# MOTORDEMO.net
KiCad netlist of a schematic drawn in Altium Designer
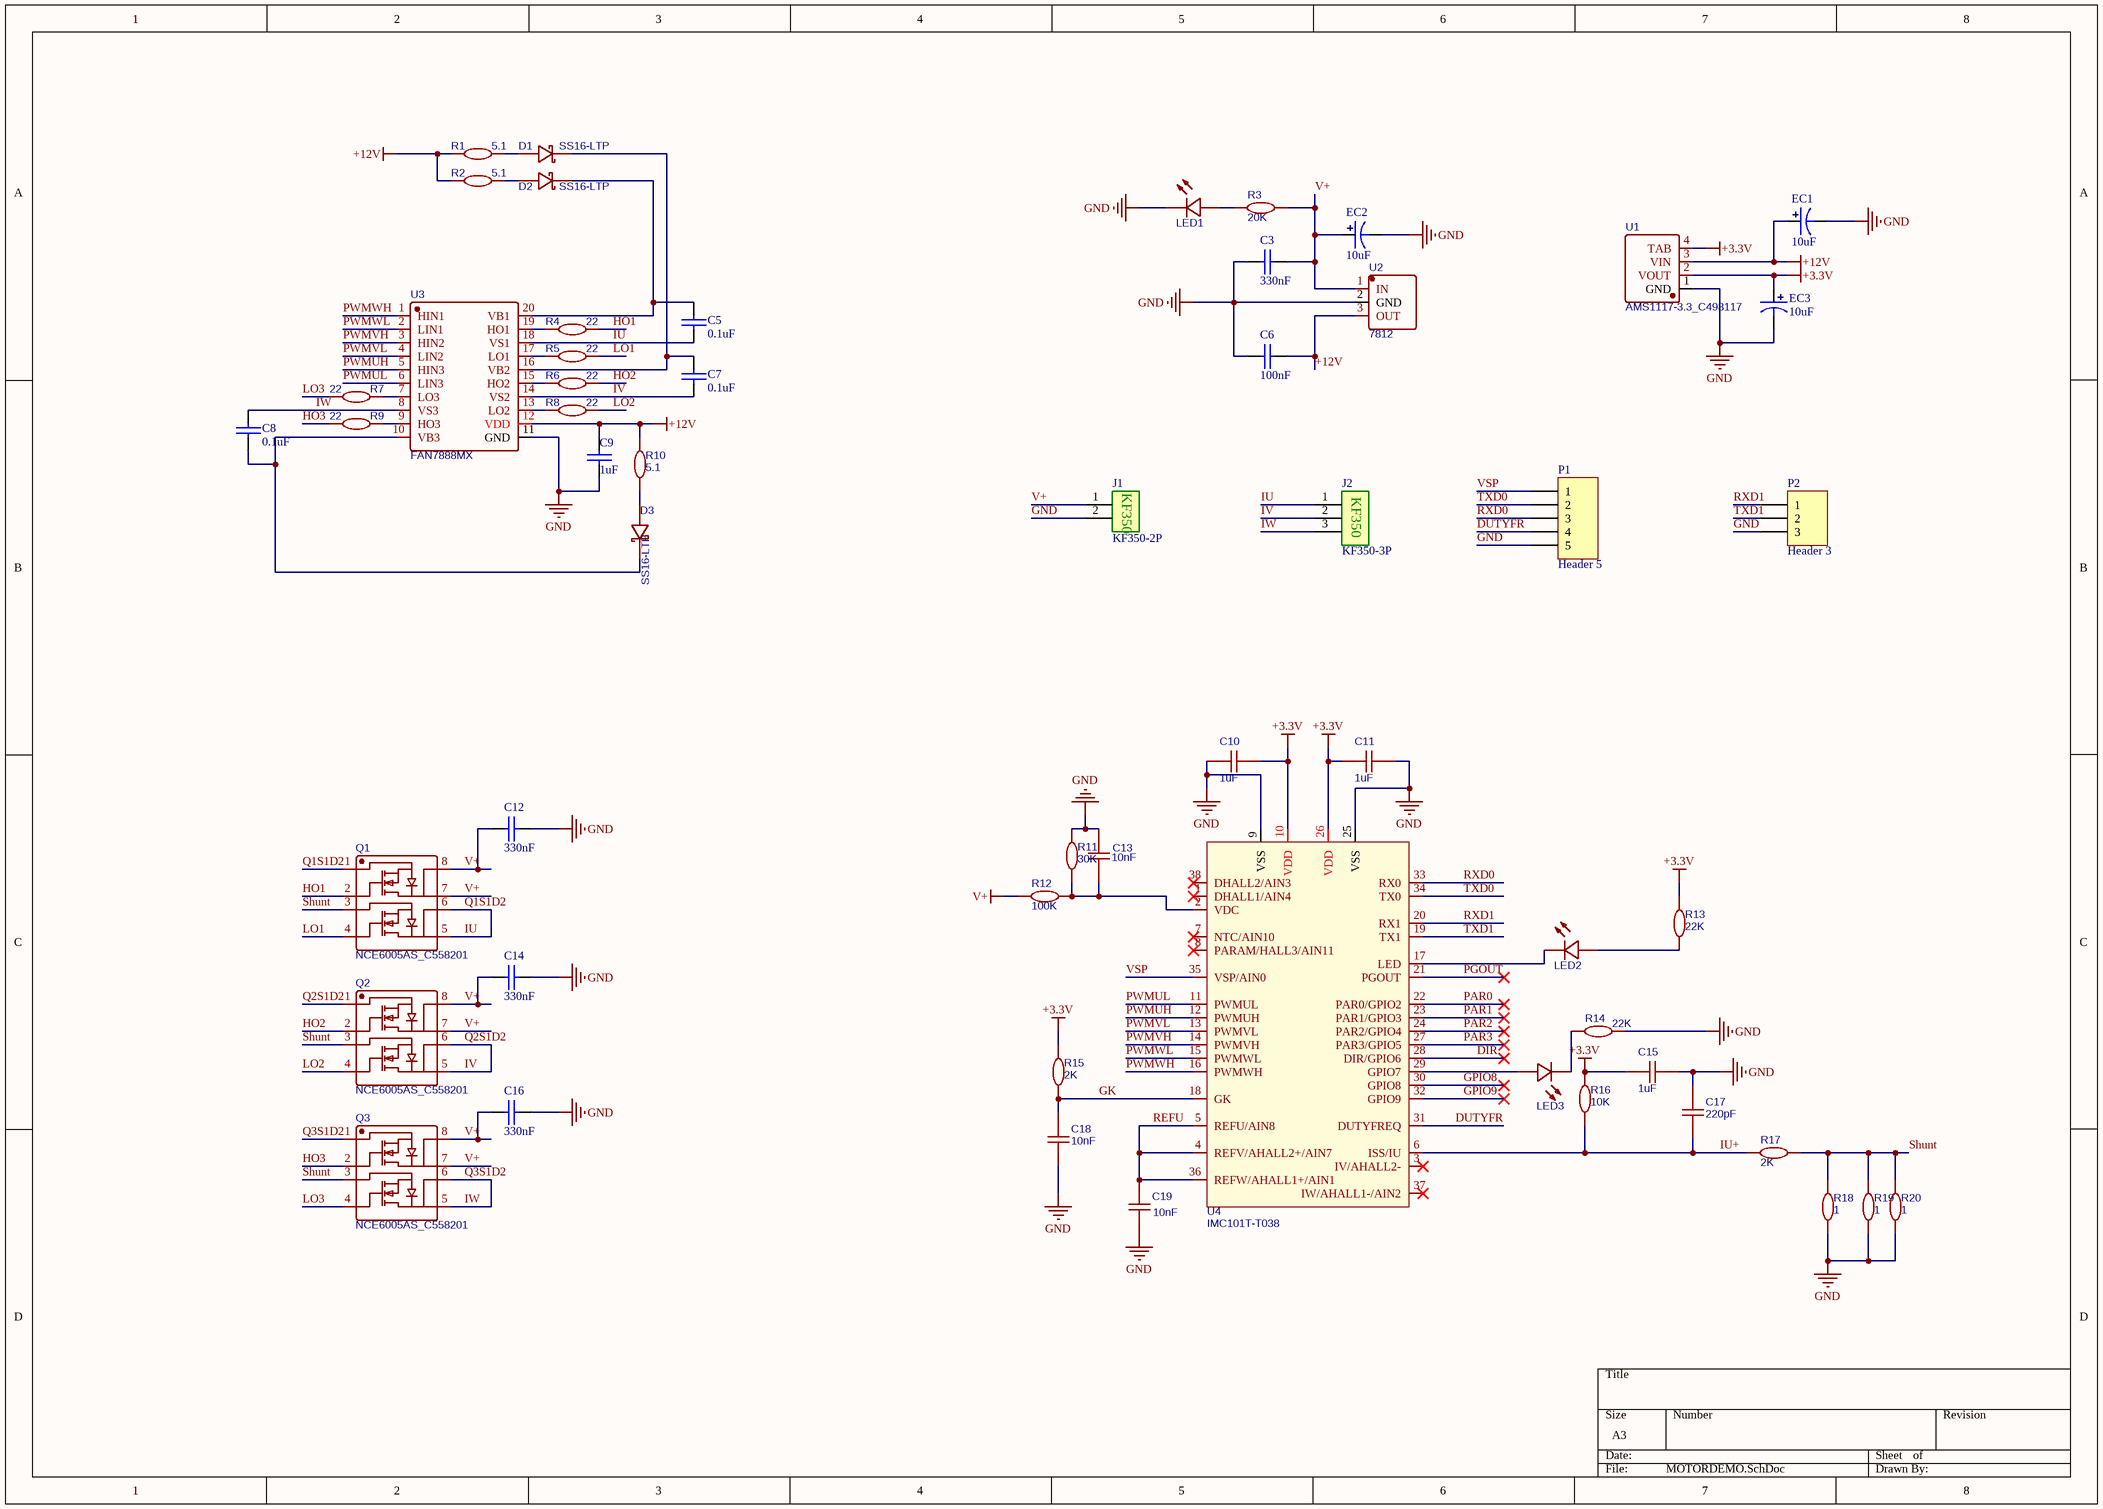
[diagram p0: MOTORDEMO.SchDoc]

(export (version "E")
  (design (tool "Eeschema 10.0.6"))
  (components
    (comp (ref "C3")
      (value "330nF")
      (footprint "C 0603_L")
      (description "Capacitor")
      (libsource (lib "原理图库") (part "CAP"))
    )
    (comp (ref "C5")
      (value "0.1uF")
      (footprint "C 0603_L")
      (description "Capacitor")
      (libsource (lib "原理图库") (part "CAP"))
    )
    (comp (ref "C6")
      (value "100nF")
      (footprint "C 0603_L")
      (description "Capacitor")
      (libsource (lib "原理图库") (part "CAP"))
    )
    (comp (ref "C7")
      (value "0.1uF")
      (footprint "C 0603_L")
      (description "Capacitor")
      (libsource (lib "原理图库") (part "CAP"))
    )
    (comp (ref "C8")
      (value "0.1uF")
      (footprint "C 0603_L")
      (description "Capacitor")
      (libsource (lib "原理图库") (part "CAP"))
    )
    (comp (ref "C9")
      (value "1uF")
      (footprint "C 0603_L")
      (description "Capacitor")
      (libsource (lib "原理图库") (part "CAP"))
    )
    (comp (ref "C10")
      (value "1uF")
      (footprint "C0603")
      (fields
        (field (name "BOM_MANUFACTURER PART") "CL10B104KC8NNNC")
        (field (name "BOM_SUPPLIER PART") "C15725")
      )
      (libsource (lib "motor") (part "100nF"))
    )
    (comp (ref "C11")
      (value "1uF")
      (footprint "C0603")
      (fields
        (field (name "BOM_MANUFACTURER PART") "CL10B104KC8NNNC")
        (field (name "BOM_SUPPLIER PART") "C15725")
      )
      (libsource (lib "motor") (part "100nF"))
    )
    (comp (ref "C12")
      (value "330nF")
      (footprint "C 0603_L")
      (description "Capacitor")
      (libsource (lib "原理图库") (part "CAP"))
    )
    (comp (ref "C13")
      (value "10nF")
      (footprint "C0603")
      (fields
        (field (name "BOM_MANUFACTURER PART") "CL10B104KC8NNNC")
        (field (name "BOM_SUPPLIER PART") "C15725")
      )
      (libsource (lib "motor") (part "100nF"))
    )
    (comp (ref "C14")
      (value "330nF")
      (footprint "C 0603_L")
      (description "Capacitor")
      (libsource (lib "原理图库") (part "CAP"))
    )
    (comp (ref "C15")
      (value "1uF")
      (footprint "C0603")
      (fields
        (field (name "BOM_MANUFACTURER PART") "CL10B104KC8NNNC")
        (field (name "BOM_SUPPLIER PART") "C15725")
      )
      (libsource (lib "motor") (part "100nF"))
    )
    (comp (ref "C16")
      (value "330nF")
      (footprint "C 0603_L")
      (description "Capacitor")
      (libsource (lib "原理图库") (part "CAP"))
    )
    (comp (ref "C17")
      (value "220pF")
      (footprint "C0603")
      (fields
        (field (name "BOM_MANUFACTURER PART") "CL10B104KC8NNNC")
        (field (name "BOM_SUPPLIER PART") "C15725")
      )
      (libsource (lib "motor") (part "100nF"))
    )
    (comp (ref "C18")
      (value "10nF")
      (footprint "C0603")
      (fields
        (field (name "BOM_MANUFACTURER PART") "CL10B104KC8NNNC")
        (field (name "BOM_SUPPLIER PART") "C15725")
      )
      (libsource (lib "motor") (part "100nF"))
    )
    (comp (ref "C19")
      (value "10nF")
      (footprint "C0603")
      (fields
        (field (name "BOM_MANUFACTURER PART") "CL10B104KC8NNNC")
        (field (name "BOM_SUPPLIER PART") "C15725")
      )
      (libsource (lib "motor") (part "100nF"))
    )
    (comp (ref "D1")
      (value "SS16-LTP")
      (footprint "LL-34_L3.5-W1.5-RD")
      (fields (field (name "BOM_SUPPLIER PART") "C85689"))
      (libsource (lib "motordemo") (part "SS16-LTP"))
    )
    (comp (ref "D2")
      (value "SS16-LTP")
      (footprint "LL-34_L3.5-W1.5-RD")
      (fields (field (name "BOM_SUPPLIER PART") "C85689"))
      (libsource (lib "motordemo") (part "SS16-LTP"))
    )
    (comp (ref "D3")
      (value "SS16-LTP")
      (footprint "LL-34_L3.5-W1.5-RD")
      (fields (field (name "BOM_SUPPLIER PART") "C85689"))
      (libsource (lib "motordemo") (part "SS16-LTP"))
    )
    (comp (ref "EC1")
      (value "10uF")
      (footprint "SMD-EC5.0X5.3X5.4")
      (description "贴片电解电容")
      (libsource (lib "电容") (part "SMD_ECAP"))
    )
    (comp (ref "EC2")
      (value "10uF")
      (footprint "SMD-EC5.0X5.3X5.4")
      (description "贴片电解电容")
      (libsource (lib "电容") (part "SMD_ECAP"))
    )
    (comp (ref "EC3")
      (value "10uF")
      (footprint "SMD-EC5.0X5.3X5.4")
      (description "贴片电解电容")
      (libsource (lib "电容") (part "SMD_ECAP"))
    )
    (comp (ref "J1") (value "KF350-2P") (footprint "KF350-2P") (libsource (lib "KF350") (part "KF350-2P")))
    (comp (ref "J2") (value "KF350-3P") (footprint "KF350-3P") (libsource (lib "KF350") (part "KF350-3P")))
    (comp (ref "LED1")
      (value "LED")
      (footprint "LED0603-R-RD")
      (fields
        (field (name "BOM_SUPPLIER PART") "C181863")
        (field (name "BOM_MANUFACTURER PART") "19-213/R6W-BP2Q2B/3T")
        (field (name "CONTRIBUTOR") "LCSC")
      )
      (libsource (lib "motor") (part "LED"))
    )
    (comp (ref "LED2")
      (value "LED")
      (footprint "LED0603-R-RD")
      (fields
        (field (name "BOM_SUPPLIER PART") "C181863")
        (field (name "BOM_MANUFACTURER PART") "19-213/R6W-BP2Q2B/3T")
        (field (name "CONTRIBUTOR") "LCSC")
      )
      (libsource (lib "motor") (part "LED"))
    )
    (comp (ref "LED3")
      (value "LED")
      (footprint "LED0603-R-RD")
      (fields
        (field (name "BOM_SUPPLIER PART") "C181863")
        (field (name "BOM_MANUFACTURER PART") "19-213/R6W-BP2Q2B/3T")
        (field (name "CONTRIBUTOR") "LCSC")
      )
      (libsource (lib "motor") (part "LED"))
    )
    (comp (ref "P1")
      (value "Header 5")
      (footprint "HDR1X5")
      (description "Header, 5-Pin")
      (fields (field (name "PUBLISHER") "Altium Limited"))
      (libsource (lib "Miscellaneous Connectors") (part "Header 5"))
    )
    (comp (ref "P2")
      (value "Header 3")
      (footprint "HDR1X3")
      (description "Header, 3-Pin")
      (fields (field (name "PUBLISHER") "Altium Limited"))
      (libsource (lib "Miscellaneous Connectors") (part "Header 3"))
    )
    (comp (ref "Q1")
      (value "NCE6005AS_C558201")
      (footprint "NCE6005AS")
      (fields
        (field (name "BOM_SUPPLIER PART") "C558201")
        (field (name "BOM_MANUFACTURER PART") "NCE6005AS")
        (field (name "CONTRIBUTOR") "LCSC")
      )
      (libsource (lib "motordemo") (part "NCE6005AS_C558201"))
    )
    (comp (ref "Q2")
      (value "NCE6005AS_C558201")
      (footprint "NCE6005AS")
      (fields
        (field (name "BOM_SUPPLIER PART") "C558201")
        (field (name "BOM_MANUFACTURER PART") "NCE6005AS")
        (field (name "CONTRIBUTOR") "LCSC")
      )
      (libsource (lib "motordemo") (part "NCE6005AS_C558201"))
    )
    (comp (ref "Q3")
      (value "NCE6005AS_C558201")
      (footprint "NCE6005AS")
      (fields
        (field (name "BOM_SUPPLIER PART") "C558201")
        (field (name "BOM_MANUFACTURER PART") "NCE6005AS")
        (field (name "CONTRIBUTOR") "LCSC")
      )
      (libsource (lib "motordemo") (part "NCE6005AS_C558201"))
    )
    (comp (ref "R1")
      (value "5.1")
      (footprint "R0603")
      (fields
        (field (name "BOM_SUPPLIER PART") "C327832")
        (field (name "BOM_MANUFACTURER PART") "MR06X105JTL")
        (field (name "CONTRIBUTOR") "LCSC")
      )
      (libsource (lib "motor") (part "1M"))
    )
    (comp (ref "R2")
      (value "5.1")
      (footprint "R0603")
      (fields
        (field (name "BOM_SUPPLIER PART") "C327832")
        (field (name "BOM_MANUFACTURER PART") "MR06X105JTL")
        (field (name "CONTRIBUTOR") "LCSC")
      )
      (libsource (lib "motor") (part "1M"))
    )
    (comp (ref "R3")
      (value "20K")
      (footprint "R0603")
      (fields
        (field (name "BOM_SUPPLIER PART") "C327832")
        (field (name "BOM_MANUFACTURER PART") "MR06X105JTL")
        (field (name "CONTRIBUTOR") "LCSC")
      )
      (libsource (lib "motor") (part "1M"))
    )
    (comp (ref "R4")
      (value "22")
      (footprint "R0603")
      (fields
        (field (name "BOM_SUPPLIER PART") "C327832")
        (field (name "BOM_MANUFACTURER PART") "MR06X105JTL")
        (field (name "CONTRIBUTOR") "LCSC")
      )
      (libsource (lib "motor") (part "1M"))
    )
    (comp (ref "R5")
      (value "22")
      (footprint "R0603")
      (fields
        (field (name "BOM_SUPPLIER PART") "C327832")
        (field (name "BOM_MANUFACTURER PART") "MR06X105JTL")
        (field (name "CONTRIBUTOR") "LCSC")
      )
      (libsource (lib "motor") (part "1M"))
    )
    (comp (ref "R6")
      (value "22")
      (footprint "R0603")
      (fields
        (field (name "BOM_SUPPLIER PART") "C327832")
        (field (name "BOM_MANUFACTURER PART") "MR06X105JTL")
        (field (name "CONTRIBUTOR") "LCSC")
      )
      (libsource (lib "motor") (part "1M"))
    )
    (comp (ref "R7")
      (value "22")
      (footprint "R0603")
      (fields
        (field (name "BOM_SUPPLIER PART") "C327832")
        (field (name "BOM_MANUFACTURER PART") "MR06X105JTL")
        (field (name "CONTRIBUTOR") "LCSC")
      )
      (libsource (lib "motor") (part "1M"))
    )
    (comp (ref "R8")
      (value "22")
      (footprint "R0603")
      (fields
        (field (name "BOM_SUPPLIER PART") "C327832")
        (field (name "BOM_MANUFACTURER PART") "MR06X105JTL")
        (field (name "CONTRIBUTOR") "LCSC")
      )
      (libsource (lib "motor") (part "1M"))
    )
    (comp (ref "R9")
      (value "22")
      (footprint "R0603")
      (fields
        (field (name "BOM_SUPPLIER PART") "C327832")
        (field (name "BOM_MANUFACTURER PART") "MR06X105JTL")
        (field (name "CONTRIBUTOR") "LCSC")
      )
      (libsource (lib "motor") (part "1M"))
    )
    (comp (ref "R10")
      (value "5.1")
      (footprint "R0603")
      (fields
        (field (name "BOM_SUPPLIER PART") "C327832")
        (field (name "BOM_MANUFACTURER PART") "MR06X105JTL")
        (field (name "CONTRIBUTOR") "LCSC")
      )
      (libsource (lib "motor") (part "1M"))
    )
    (comp (ref "R11")
      (value "30K")
      (footprint "R0603")
      (fields
        (field (name "BOM_SUPPLIER PART") "C327832")
        (field (name "BOM_MANUFACTURER PART") "MR06X105JTL")
        (field (name "CONTRIBUTOR") "LCSC")
      )
      (libsource (lib "motor") (part "1M"))
    )
    (comp (ref "R12")
      (value "100K")
      (footprint "R0603")
      (fields
        (field (name "BOM_SUPPLIER PART") "C327832")
        (field (name "BOM_MANUFACTURER PART") "MR06X105JTL")
        (field (name "CONTRIBUTOR") "LCSC")
      )
      (libsource (lib "motor") (part "1M"))
    )
    (comp (ref "R13")
      (value "22K")
      (footprint "R0603")
      (fields
        (field (name "BOM_SUPPLIER PART") "C327832")
        (field (name "BOM_MANUFACTURER PART") "MR06X105JTL")
        (field (name "CONTRIBUTOR") "LCSC")
      )
      (libsource (lib "motor") (part "1M"))
    )
    (comp (ref "R14")
      (value "22K")
      (footprint "R0603")
      (fields
        (field (name "BOM_SUPPLIER PART") "C327832")
        (field (name "BOM_MANUFACTURER PART") "MR06X105JTL")
        (field (name "CONTRIBUTOR") "LCSC")
      )
      (libsource (lib "motor") (part "1M"))
    )
    (comp (ref "R15")
      (value "2K")
      (footprint "R0603")
      (fields
        (field (name "BOM_SUPPLIER PART") "C327832")
        (field (name "BOM_MANUFACTURER PART") "MR06X105JTL")
        (field (name "CONTRIBUTOR") "LCSC")
      )
      (libsource (lib "motor") (part "1M"))
    )
    (comp (ref "R16")
      (value "10K")
      (footprint "R0603")
      (fields
        (field (name "BOM_SUPPLIER PART") "C327832")
        (field (name "BOM_MANUFACTURER PART") "MR06X105JTL")
        (field (name "CONTRIBUTOR") "LCSC")
      )
      (libsource (lib "motor") (part "1M"))
    )
    (comp (ref "R17")
      (value "2K")
      (footprint "R0603")
      (fields
        (field (name "BOM_SUPPLIER PART") "C327832")
        (field (name "BOM_MANUFACTURER PART") "MR06X105JTL")
        (field (name "CONTRIBUTOR") "LCSC")
      )
      (libsource (lib "motor") (part "1M"))
    )
    (comp (ref "R18")
      (value "1")
      (footprint "R1206")
      (fields
        (field (name "BOM_SUPPLIER PART") "C327832")
        (field (name "BOM_MANUFACTURER PART") "MR06X105JTL")
        (field (name "CONTRIBUTOR") "LCSC")
      )
      (libsource (lib "motor") (part "1M"))
    )
    (comp (ref "R19")
      (value "1")
      (footprint "R1206")
      (fields
        (field (name "BOM_SUPPLIER PART") "C327832")
        (field (name "BOM_MANUFACTURER PART") "MR06X105JTL")
        (field (name "CONTRIBUTOR") "LCSC")
      )
      (libsource (lib "motor") (part "1M"))
    )
    (comp (ref "R20")
      (value "1")
      (footprint "R1206")
      (fields
        (field (name "BOM_SUPPLIER PART") "C327832")
        (field (name "BOM_MANUFACTURER PART") "MR06X105JTL")
        (field (name "CONTRIBUTOR") "LCSC")
      )
      (libsource (lib "motor") (part "1M"))
    )
    (comp (ref "U1")
      (value "AMS1117-3.3_C498117")
      (footprint "PG-SOT223-4_L6.5-W3.5-P2.30-LS7.0-BR")
      (fields
        (field (name "BOM_SUPPLIER PART") "C498117")
        (field (name "BOM_MANUFACTURER PART") "AMS1117-3.3")
        (field (name "CONTRIBUTOR") "LCSC")
      )
      (libsource (lib "20200123") (part "AMS1117-3.3_C498117"))
    )
    (comp (ref "U2")
      (value "7812")
      (footprint "TO-220-3_L10.0-W4.5-P2.54-L")
      (fields (field (name "BOM_SUPPLIER PART") "C358369") (field (name "CONTRIBUTOR") "LCSC"))
      (libsource (lib "motordemo") (part "7812"))
    )
    (comp (ref "U3")
      (value "FAN7888MX")
      (footprint "FAN7888")
      (fields (field (name "BOM_SUPPLIER PART") "C258167") (field (name "CONTRIBUTOR") "LCSC"))
      (libsource (lib "motordemo") (part "FAN7888MX"))
    )
    (comp (ref "U4")
      (value "IMC101T-T038")
      (footprint "IMC101T-T038")
      (fields (field (name "BOM_SUPPLIER PART") "C536267") (field (name "CONTRIBUTOR") "LCSC"))
      (libsource (lib "motor") (part "IMC101T-T038"))
    )
  )
  (nets
    (net (code "1") (name "+3.3V") (class "Default")
      (node (ref "C10") (pin "1") (pinfunction "1_1") (pintype "passive"))
      (node (ref "C11") (pin "2") (pinfunction "2_2") (pintype "passive"))
      (node (ref "C15") (pin "1") (pinfunction "1_1") (pintype "passive"))
      (node (ref "EC3") (pin "1") (pinfunction "1_1") (pintype "passive"))
      (node (ref "R13") (pin "2") (pinfunction "2_2") (pintype "passive"))
      (node (ref "R15") (pin "1") (pinfunction "1_1") (pintype "passive"))
      (node (ref "R16") (pin "1") (pinfunction "1_1") (pintype "passive"))
      (node (ref "U1") (pin "2") (pinfunction "VOUT_2") (pintype "passive"))
      (node (ref "U1") (pin "4") (pinfunction "TAB_4") (pintype "passive"))
      (node (ref "U4") (pin "10") (pinfunction "VDD_10") (pintype "passive"))
      (node (ref "U4") (pin "26") (pinfunction "VDD_26") (pintype "passive"))
    )
    (net (code "2") (name "+12V") (class "Default")
      (node (ref "C6") (pin "1") (pinfunction "1_1") (pintype "passive"))
      (node (ref "C9") (pin "2") (pinfunction "2_2") (pintype "passive"))
      (node (ref "EC1") (pin "1") (pinfunction "1_1") (pintype "passive"))
      (node (ref "R1") (pin "2") (pinfunction "2_2") (pintype "passive"))
      (node (ref "R10") (pin "1") (pinfunction "1_1") (pintype "passive"))
      (node (ref "R2") (pin "2") (pinfunction "2_2") (pintype "passive"))
      (node (ref "U1") (pin "3") (pinfunction "VIN_3") (pintype "passive"))
      (node (ref "U2") (pin "3") (pinfunction "OUT_3") (pintype "passive"))
      (node (ref "U3") (pin "12") (pinfunction "VDD_12") (pintype "passive"))
    )
    (net (code "3") (name "/DIR") (class "Default")
      (node (ref "U4") (pin "28") (pinfunction "DIR/GPIO6_28") (pintype "passive+no_connect"))
    )
    (net (code "4") (name "/DUTYFR") (class "Default")
      (node (ref "P1") (pin "4") (pinfunction "4_4") (pintype "passive"))
      (node (ref "U4") (pin "31") (pinfunction "DUTYFREQ_31") (pintype "passive"))
    )
    (net (code "5") (name "/GK") (class "Default")
      (node (ref "C18") (pin "2") (pinfunction "2_2") (pintype "passive"))
      (node (ref "R15") (pin "2") (pinfunction "2_2") (pintype "passive"))
      (node (ref "U4") (pin "18") (pinfunction "GK_18") (pintype "passive"))
    )
    (net (code "6") (name "/GPIO8") (class "Default")
      (node (ref "U4") (pin "30") (pinfunction "GPIO8_30") (pintype "passive+no_connect"))
    )
    (net (code "7") (name "/GPIO9") (class "Default")
      (node (ref "U4") (pin "32") (pinfunction "GPIO9_32") (pintype "passive+no_connect"))
    )
    (net (code "8") (name "/HO1") (class "Default")
      (node (ref "Q1") (pin "2") (pinfunction "2_2") (pintype "passive"))
      (node (ref "R4") (pin "1") (pinfunction "1_1") (pintype "passive"))
    )
    (net (code "9") (name "/HO2") (class "Default")
      (node (ref "Q2") (pin "2") (pinfunction "2_2") (pintype "passive"))
      (node (ref "R6") (pin "1") (pinfunction "1_1") (pintype "passive"))
    )
    (net (code "10") (name "/HO3") (class "Default")
      (node (ref "Q3") (pin "2") (pinfunction "2_2") (pintype "passive"))
      (node (ref "R9") (pin "2") (pinfunction "2_2") (pintype "passive"))
    )
    (net (code "11") (name "/IU") (class "Default")
      (node (ref "C5") (pin "1") (pinfunction "1_1") (pintype "passive"))
      (node (ref "J2") (pin "1") (pinfunction "1_1") (pintype "passive"))
      (node (ref "Q1") (pin "1") (pinfunction "1_1") (pintype "passive"))
      (node (ref "Q1") (pin "5") (pinfunction "5_5") (pintype "passive"))
      (node (ref "Q1") (pin "6") (pinfunction "6_6") (pintype "passive"))
      (node (ref "U3") (pin "18") (pinfunction "VS1_18") (pintype "passive"))
    )
    (net (code "12") (name "/IU+") (class "Default")
      (node (ref "C17") (pin "1") (pinfunction "1_1") (pintype "passive"))
      (node (ref "R16") (pin "2") (pinfunction "2_2") (pintype "passive"))
      (node (ref "R17") (pin "1") (pinfunction "1_1") (pintype "passive"))
      (node (ref "U4") (pin "6") (pinfunction "ISS/IU_6") (pintype "passive"))
    )
    (net (code "13") (name "/IV") (class "Default")
      (node (ref "C7") (pin "1") (pinfunction "1_1") (pintype "passive"))
      (node (ref "J2") (pin "2") (pinfunction "2_2") (pintype "passive"))
      (node (ref "Q2") (pin "1") (pinfunction "1_1") (pintype "passive"))
      (node (ref "Q2") (pin "5") (pinfunction "5_5") (pintype "passive"))
      (node (ref "Q2") (pin "6") (pinfunction "6_6") (pintype "passive"))
      (node (ref "U3") (pin "14") (pinfunction "VS2_14") (pintype "passive"))
    )
    (net (code "14") (name "/IW") (class "Default")
      (node (ref "C8") (pin "2") (pinfunction "2_2") (pintype "passive"))
      (node (ref "J2") (pin "3") (pinfunction "3_3") (pintype "passive"))
      (node (ref "Q3") (pin "1") (pinfunction "1_1") (pintype "passive"))
      (node (ref "Q3") (pin "5") (pinfunction "5_5") (pintype "passive"))
      (node (ref "Q3") (pin "6") (pinfunction "6_6") (pintype "passive"))
      (node (ref "U3") (pin "8") (pinfunction "VS3_8") (pintype "passive"))
    )
    (net (code "15") (name "/LO1") (class "Default")
      (node (ref "Q1") (pin "4") (pinfunction "4_4") (pintype "passive"))
      (node (ref "R5") (pin "1") (pinfunction "1_1") (pintype "passive"))
    )
    (net (code "16") (name "/LO2") (class "Default")
      (node (ref "Q2") (pin "4") (pinfunction "4_4") (pintype "passive"))
      (node (ref "R8") (pin "1") (pinfunction "1_1") (pintype "passive"))
    )
    (net (code "17") (name "/LO3") (class "Default")
      (node (ref "Q3") (pin "4") (pinfunction "4_4") (pintype "passive"))
      (node (ref "R7") (pin "2") (pinfunction "2_2") (pintype "passive"))
    )
    (net (code "18") (name "/PAR0") (class "Default")
      (node (ref "U4") (pin "22") (pinfunction "PAR0/GPIO2_22") (pintype "passive+no_connect"))
    )
    (net (code "19") (name "/PAR1") (class "Default")
      (node (ref "U4") (pin "23") (pinfunction "PAR1/GPIO3_23") (pintype "passive+no_connect"))
    )
    (net (code "20") (name "/PAR2") (class "Default")
      (node (ref "U4") (pin "24") (pinfunction "PAR2/GPIO4_24") (pintype "passive+no_connect"))
    )
    (net (code "21") (name "/PAR3") (class "Default")
      (node (ref "U4") (pin "27") (pinfunction "PAR3/GPIO5_27") (pintype "passive+no_connect"))
    )
    (net (code "22") (name "/PGOUT") (class "Default")
      (node (ref "U4") (pin "21") (pinfunction "PGOUT_21") (pintype "passive+no_connect"))
    )
    (net (code "23") (name "/PWMUH") (class "Default")
      (node (ref "U3") (pin "5") (pinfunction "HIN3_5") (pintype "passive"))
      (node (ref "U4") (pin "12") (pinfunction "PWMUH_12") (pintype "passive"))
    )
    (net (code "24") (name "/PWMUL") (class "Default")
      (node (ref "U3") (pin "6") (pinfunction "LIN3_6") (pintype "passive"))
      (node (ref "U4") (pin "11") (pinfunction "PWMUL_11") (pintype "passive"))
    )
    (net (code "25") (name "/PWMVH") (class "Default")
      (node (ref "U3") (pin "3") (pinfunction "HIN2_3") (pintype "passive"))
      (node (ref "U4") (pin "14") (pinfunction "PWMVH_14") (pintype "passive"))
    )
    (net (code "26") (name "/PWMVL") (class "Default")
      (node (ref "U3") (pin "4") (pinfunction "LIN2_4") (pintype "passive"))
      (node (ref "U4") (pin "13") (pinfunction "PWMVL_13") (pintype "passive"))
    )
    (net (code "27") (name "/PWMWH") (class "Default")
      (node (ref "U3") (pin "1") (pinfunction "HIN1_1") (pintype "passive"))
      (node (ref "U4") (pin "16") (pinfunction "PWMWH_16") (pintype "passive"))
    )
    (net (code "28") (name "/PWMWL") (class "Default")
      (node (ref "U3") (pin "2") (pinfunction "LIN1_2") (pintype "passive"))
      (node (ref "U4") (pin "15") (pinfunction "PWMWL_15") (pintype "passive"))
    )
    (net (code "29") (name "/REFU") (class "Default")
      (node (ref "C19") (pin "2") (pinfunction "2_2") (pintype "passive"))
      (node (ref "U4") (pin "36") (pinfunction "REFW/AHALL1+/AIN1_36") (pintype "passive"))
      (node (ref "U4") (pin "4") (pinfunction "REFV/AHALL2+/AIN7_4") (pintype "passive"))
      (node (ref "U4") (pin "5") (pinfunction "REFU/AIN8_5") (pintype "passive"))
    )
    (net (code "30") (name "/RXD0") (class "Default")
      (node (ref "P1") (pin "3") (pinfunction "3_3") (pintype "passive"))
      (node (ref "U4") (pin "33") (pinfunction "RX0_33") (pintype "passive"))
    )
    (net (code "31") (name "/RXD1") (class "Default")
      (node (ref "P2") (pin "1") (pinfunction "1_1") (pintype "passive"))
      (node (ref "U4") (pin "20") (pinfunction "RX1_20") (pintype "passive"))
    )
    (net (code "32") (name "/Shunt") (class "Default")
      (node (ref "Q1") (pin "3") (pinfunction "3_3") (pintype "passive"))
      (node (ref "Q2") (pin "3") (pinfunction "3_3") (pintype "passive"))
      (node (ref "Q3") (pin "3") (pinfunction "3_3") (pintype "passive"))
      (node (ref "R17") (pin "2") (pinfunction "2_2") (pintype "passive"))
      (node (ref "R18") (pin "2") (pinfunction "2_2") (pintype "passive"))
      (node (ref "R19") (pin "2") (pinfunction "2_2") (pintype "passive"))
      (node (ref "R20") (pin "2") (pinfunction "2_2") (pintype "passive"))
    )
    (net (code "33") (name "/TXD0") (class "Default")
      (node (ref "P1") (pin "2") (pinfunction "2_2") (pintype "passive"))
      (node (ref "U4") (pin "34") (pinfunction "TX0_34") (pintype "passive"))
    )
    (net (code "34") (name "/TXD1") (class "Default")
      (node (ref "P2") (pin "2") (pinfunction "2_2") (pintype "passive"))
      (node (ref "U4") (pin "19") (pinfunction "TX1_19") (pintype "passive"))
    )
    (net (code "35") (name "/VSP") (class "Default")
      (node (ref "P1") (pin "1") (pinfunction "1_1") (pintype "passive"))
      (node (ref "U4") (pin "35") (pinfunction "VSP/AIN0_35") (pintype "passive"))
    )
    (net (code "36") (name "GND") (class "Default")
      (node (ref "C10") (pin "2") (pinfunction "2_2") (pintype "passive"))
      (node (ref "C11") (pin "1") (pinfunction "1_1") (pintype "passive"))
      (node (ref "C12") (pin "1") (pinfunction "1_1") (pintype "passive"))
      (node (ref "C13") (pin "2") (pinfunction "2_2") (pintype "passive"))
      (node (ref "C14") (pin "1") (pinfunction "1_1") (pintype "passive"))
      (node (ref "C15") (pin "2") (pinfunction "2_2") (pintype "passive"))
      (node (ref "C16") (pin "1") (pinfunction "1_1") (pintype "passive"))
      (node (ref "C17") (pin "2") (pinfunction "2_2") (pintype "passive"))
      (node (ref "C18") (pin "1") (pinfunction "1_1") (pintype "passive"))
      (node (ref "C19") (pin "1") (pinfunction "1_1") (pintype "passive"))
      (node (ref "C3") (pin "2") (pinfunction "2_2") (pintype "passive"))
      (node (ref "C6") (pin "2") (pinfunction "2_2") (pintype "passive"))
      (node (ref "C9") (pin "1") (pinfunction "1_1") (pintype "passive"))
      (node (ref "EC1") (pin "2") (pinfunction "2_2") (pintype "passive"))
      (node (ref "EC2") (pin "2") (pinfunction "2_2") (pintype "passive"))
      (node (ref "EC3") (pin "2") (pinfunction "2_2") (pintype "passive"))
      (node (ref "J1") (pin "2") (pinfunction "2_2") (pintype "passive"))
      (node (ref "LED1") (pin "2") (pinfunction "2_2") (pintype "passive"))
      (node (ref "P1") (pin "5") (pinfunction "5_5") (pintype "passive"))
      (node (ref "P2") (pin "3") (pinfunction "3_3") (pintype "passive"))
      (node (ref "R11") (pin "1") (pinfunction "1_1") (pintype "passive"))
      (node (ref "R14") (pin "1") (pinfunction "1_1") (pintype "passive"))
      (node (ref "R18") (pin "1") (pinfunction "1_1") (pintype "passive"))
      (node (ref "R19") (pin "1") (pinfunction "1_1") (pintype "passive"))
      (node (ref "R20") (pin "1") (pinfunction "1_1") (pintype "passive"))
      (node (ref "U1") (pin "1") (pinfunction "GND_1") (pintype "passive"))
      (node (ref "U2") (pin "2") (pinfunction "GND_2") (pintype "passive"))
      (node (ref "U3") (pin "11") (pinfunction "GND_11") (pintype "passive"))
      (node (ref "U4") (pin "25") (pinfunction "VSS_25") (pintype "passive"))
      (node (ref "U4") (pin "9") (pinfunction "VSS_9") (pintype "passive"))
    )
    (net (code "37") (name "Net-(D1-A)") (class "Default")
      (node (ref "D1") (pin "2") (pinfunction "A_2") (pintype "passive"))
      (node (ref "R1") (pin "1") (pinfunction "1_1") (pintype "passive"))
    )
    (net (code "38") (name "Net-(D1-C)") (class "Default")
      (node (ref "C7") (pin "2") (pinfunction "2_2") (pintype "passive"))
      (node (ref "D1") (pin "1") (pinfunction "C_1") (pintype "passive"))
      (node (ref "U3") (pin "16") (pinfunction "VB2_16") (pintype "passive"))
    )
    (net (code "39") (name "Net-(D2-A)") (class "Default")
      (node (ref "D2") (pin "2") (pinfunction "A_2") (pintype "passive"))
      (node (ref "R2") (pin "1") (pinfunction "1_1") (pintype "passive"))
    )
    (net (code "40") (name "Net-(D2-C)") (class "Default")
      (node (ref "C5") (pin "2") (pinfunction "2_2") (pintype "passive"))
      (node (ref "D2") (pin "1") (pinfunction "C_1") (pintype "passive"))
      (node (ref "U3") (pin "20") (pinfunction "VB1_20") (pintype "passive"))
    )
    (net (code "41") (name "Net-(D3-A)") (class "Default")
      (node (ref "D3") (pin "2") (pinfunction "A_2") (pintype "passive"))
      (node (ref "R10") (pin "2") (pinfunction "2_2") (pintype "passive"))
    )
    (net (code "42") (name "Net-(D3-C)") (class "Default")
      (node (ref "C8") (pin "1") (pinfunction "1_1") (pintype "passive"))
      (node (ref "D3") (pin "1") (pinfunction "C_1") (pintype "passive"))
      (node (ref "U3") (pin "10") (pinfunction "VB3_10") (pintype "passive"))
    )
    (net (code "43") (name "Net-(LED1-Pad1)") (class "Default")
      (node (ref "LED1") (pin "1") (pinfunction "1_1") (pintype "passive"))
      (node (ref "R3") (pin "2") (pinfunction "2_2") (pintype "passive"))
    )
    (net (code "44") (name "Net-(LED2-Pad1)") (class "Default")
      (node (ref "LED2") (pin "1") (pinfunction "1_1") (pintype "passive"))
      (node (ref "R13") (pin "1") (pinfunction "1_1") (pintype "passive"))
    )
    (net (code "45") (name "Net-(LED3-Pad2)") (class "Default")
      (node (ref "LED3") (pin "2") (pinfunction "2_2") (pintype "passive"))
      (node (ref "R14") (pin "2") (pinfunction "2_2") (pintype "passive"))
    )
    (net (code "46") (name "Net-(U3-HO1)") (class "Default")
      (node (ref "R4") (pin "2") (pinfunction "2_2") (pintype "passive"))
      (node (ref "U3") (pin "19") (pinfunction "HO1_19") (pintype "passive"))
    )
    (net (code "47") (name "Net-(U3-HO2)") (class "Default")
      (node (ref "R6") (pin "2") (pinfunction "2_2") (pintype "passive"))
      (node (ref "U3") (pin "15") (pinfunction "HO2_15") (pintype "passive"))
    )
    (net (code "48") (name "Net-(U3-HO3)") (class "Default")
      (node (ref "R9") (pin "1") (pinfunction "1_1") (pintype "passive"))
      (node (ref "U3") (pin "9") (pinfunction "HO3_9") (pintype "passive"))
    )
    (net (code "49") (name "Net-(U3-LO1)") (class "Default")
      (node (ref "R5") (pin "2") (pinfunction "2_2") (pintype "passive"))
      (node (ref "U3") (pin "17") (pinfunction "LO1_17") (pintype "passive"))
    )
    (net (code "50") (name "Net-(U3-LO2)") (class "Default")
      (node (ref "R8") (pin "2") (pinfunction "2_2") (pintype "passive"))
      (node (ref "U3") (pin "13") (pinfunction "LO2_13") (pintype "passive"))
    )
    (net (code "51") (name "Net-(U3-LO3)") (class "Default")
      (node (ref "R7") (pin "1") (pinfunction "1_1") (pintype "passive"))
      (node (ref "U3") (pin "7") (pinfunction "LO3_7") (pintype "passive"))
    )
    (net (code "52") (name "Net-(U4-GPIO7)") (class "Default")
      (node (ref "LED3") (pin "1") (pinfunction "1_1") (pintype "passive"))
      (node (ref "U4") (pin "29") (pinfunction "GPIO7_29") (pintype "passive"))
    )
    (net (code "53") (name "Net-(U4-LED)") (class "Default")
      (node (ref "LED2") (pin "2") (pinfunction "2_2") (pintype "passive"))
      (node (ref "U4") (pin "17") (pinfunction "LED_17") (pintype "passive"))
    )
    (net (code "54") (name "Net-(U4-VDC)") (class "Default")
      (node (ref "C13") (pin "1") (pinfunction "1_1") (pintype "passive"))
      (node (ref "R11") (pin "2") (pinfunction "2_2") (pintype "passive"))
      (node (ref "R12") (pin "1") (pinfunction "1_1") (pintype "passive"))
      (node (ref "U4") (pin "2") (pinfunction "VDC_2") (pintype "passive"))
    )
    (net (code "55") (name "V+") (class "Default")
      (node (ref "C12") (pin "2") (pinfunction "2_2") (pintype "passive"))
      (node (ref "C14") (pin "2") (pinfunction "2_2") (pintype "passive"))
      (node (ref "C16") (pin "2") (pinfunction "2_2") (pintype "passive"))
      (node (ref "C3") (pin "1") (pinfunction "1_1") (pintype "passive"))
      (node (ref "EC2") (pin "1") (pinfunction "1_1") (pintype "passive"))
      (node (ref "J1") (pin "1") (pinfunction "1_1") (pintype "passive"))
      (node (ref "Q1") (pin "7") (pinfunction "7_7") (pintype "passive"))
      (node (ref "Q1") (pin "8") (pinfunction "8_8") (pintype "passive"))
      (node (ref "Q2") (pin "7") (pinfunction "7_7") (pintype "passive"))
      (node (ref "Q2") (pin "8") (pinfunction "8_8") (pintype "passive"))
      (node (ref "Q3") (pin "7") (pinfunction "7_7") (pintype "passive"))
      (node (ref "Q3") (pin "8") (pinfunction "8_8") (pintype "passive"))
      (node (ref "R12") (pin "2") (pinfunction "2_2") (pintype "passive"))
      (node (ref "R3") (pin "1") (pinfunction "1_1") (pintype "passive"))
      (node (ref "U2") (pin "1") (pinfunction "IN_1") (pintype "passive"))
    )
    (net (code "56") (name "unconnected-(U4-DHALL1{slash}AIN4-Pad1)") (class "Default")
      (node (ref "U4") (pin "1") (pinfunction "DHALL1/AIN4_1") (pintype "passive+no_connect"))
    )
    (net (code "57") (name "unconnected-(U4-DHALL2{slash}AIN3-Pad38)") (class "Default")
      (node (ref "U4") (pin "38") (pinfunction "DHALL2/AIN3_38") (pintype "passive+no_connect"))
    )
    (net (code "58") (name "unconnected-(U4-IV{slash}AHALL2--Pad3)") (class "Default")
      (node (ref "U4") (pin "3") (pinfunction "IV/AHALL2-_3") (pintype "passive+no_connect"))
    )
    (net (code "59") (name "unconnected-(U4-IW{slash}AHALL1-{slash}AIN2-Pad37)") (class "Default")
      (node (ref "U4") (pin "37") (pinfunction "IW/AHALL1-/AIN2_37") (pintype "passive+no_connect"))
    )
    (net (code "60") (name "unconnected-(U4-NTC{slash}AIN10-Pad7)") (class "Default")
      (node (ref "U4") (pin "7") (pinfunction "NTC/AIN10_7") (pintype "passive+no_connect"))
    )
    (net (code "61") (name "unconnected-(U4-PARAM{slash}HALL3{slash}AIN11-Pad8)") (class "Default")
      (node (ref "U4") (pin "8") (pinfunction "PARAM/HALL3/AIN11_8") (pintype "passive+no_connect"))
    )
  )
)
